# Signal_Conditioning.net
KiCad netlist of a schematic drawn in Altium Designer
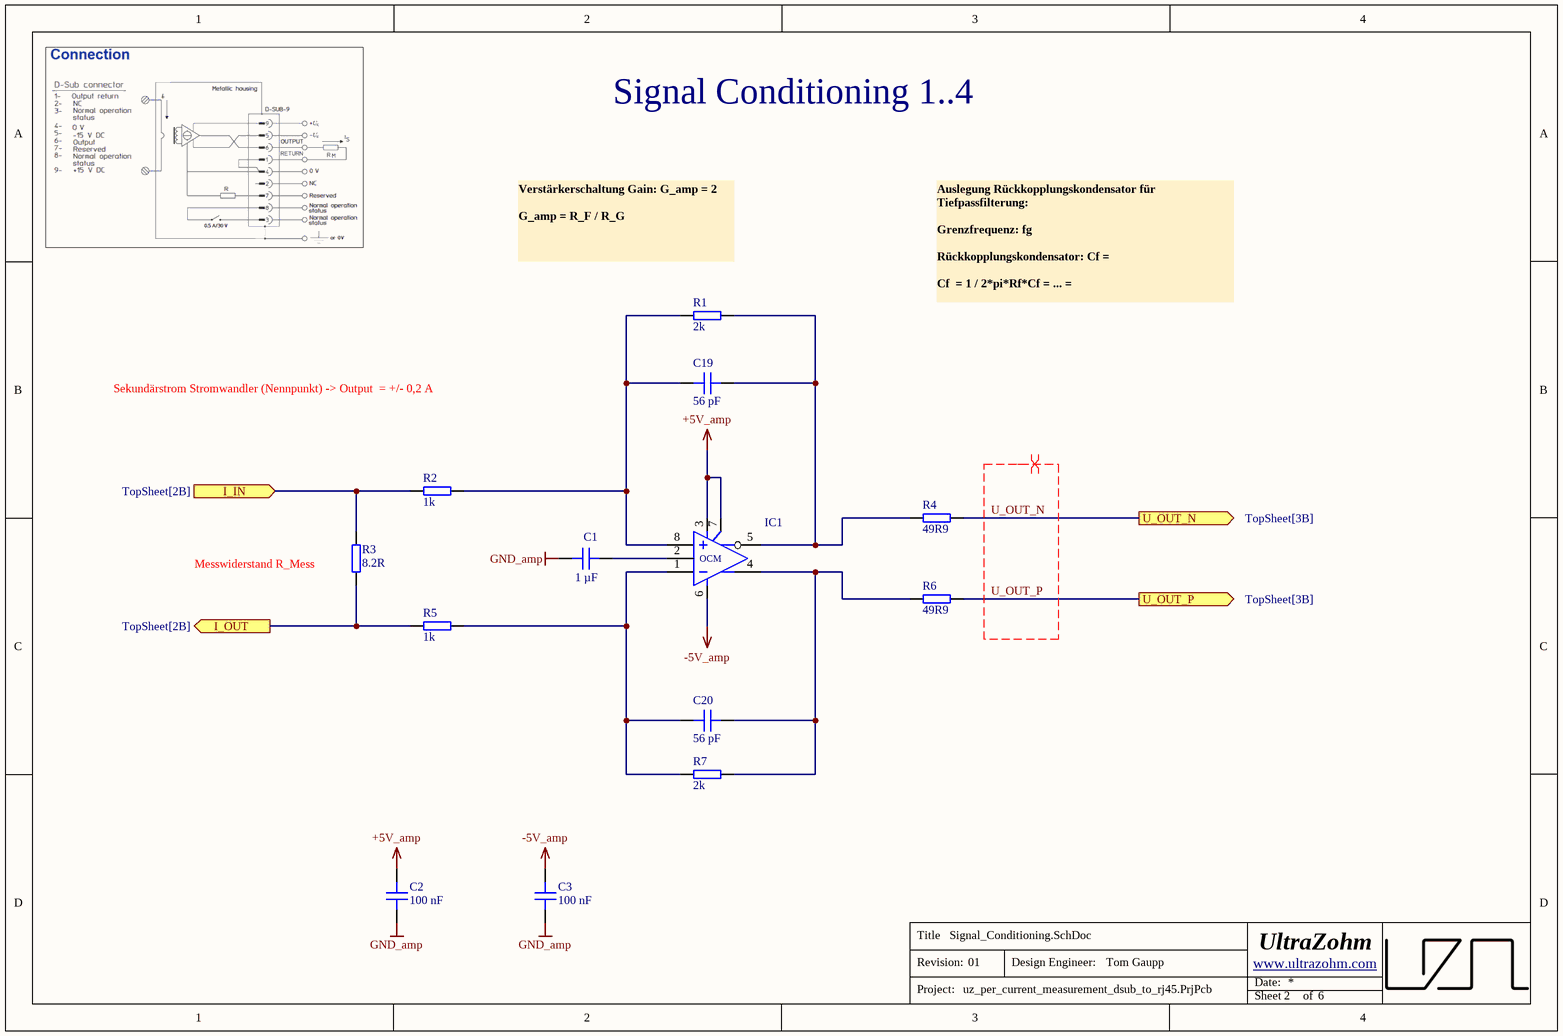
[diagram p0: Signal_Conditioning.SchDoc]

(export (version "E")
  (design (tool "Eeschema 10.0.6"))
  (components
    (comp (ref "C1")
      (value "1 µF")
      (footprint "C_0603")
      (description "50V 1uF X5R ±10% 0603  Multilayer Ceramic Capacitors MLCC - SMD/SMT ROHS")
      (fields
        (field (name "MANUFACTURER") "Samsung Electro-Mechanics")
        (field (name "MANUFACTURER PART NUMBER") "CL10A105KB8NNNC")
        (field (name "CREATED FROM") "MGremer")
      )
      (libsource (lib "user") (part "Capacitor"))
    )
    (comp (ref "C2")
      (value "100 nF")
      (footprint "C_0603")
      (description "Capacitor 0603, 50 VDC, 100nF, X7R")
      (fields
        (field (name "MANUFACTURER PART NUMBER") "C0603C104K5RAC3121")
        (field (name "MANUFACTURER") "KEMET")
        (field (name "CREATED FROM") "DHufnagel")
      )
      (libsource (lib "user") (part "Capacitor"))
    )
    (comp (ref "C3")
      (value "100 nF")
      (footprint "C_0603")
      (description "Capacitor 0603, 50 VDC, 100nF, X7R")
      (fields
        (field (name "MANUFACTURER PART NUMBER") "C0603C104K5RAC3121")
        (field (name "MANUFACTURER") "KEMET")
        (field (name "CREATED FROM") "DHufnagel")
      )
      (libsource (lib "user") (part "Capacitor"))
    )
    (comp (ref "C19")
      (value "56 pF")
      (footprint "C_0603")
      (description "Capacitor 0603, 50 VDC, 56 pF, C0G")
      (fields
        (field (name "MANUFACTURER PART NUMBER") "CL10C560JB8NNNC")
        (field (name "MANUFACTURER") "Samsung Electro-Mechanics")
        (field (name "CREATED FROM") "DHufnagel")
      )
      (libsource (lib "user") (part "Capacitor"))
    )
    (comp (ref "C20")
      (value "56 pF")
      (footprint "C_0603")
      (description "Capacitor 0603, 50 VDC, 56 pF, C0G")
      (fields
        (field (name "MANUFACTURER PART NUMBER") "CL10C560JB8NNNC")
        (field (name "MANUFACTURER") "Samsung Electro-Mechanics")
        (field (name "CREATED FROM") "DHufnagel")
      )
      (libsource (lib "user") (part "Capacitor"))
    )
    (comp (ref "IC1")
      (value "ADA4940-1ARZ-R7")
      (footprint "SOIC-8-N")
      (description "Differential ADC Driver")
      (fields
        (field (name "MANUFACTURER") "Analog Devices")
        (field (name "LCSC PART NUMBER") "C730049")
        (field (name "CREATED FROM") "MGremer")
      )
      (libsource (lib "user") (part "ADA4940-1ARZ"))
    )
    (comp (ref "R1")
      (value "2k")
      (footprint "RES 1206_3216")
      (description "2kΩ ±0.1% 250mW 1206")
      (fields
        (field (name "MANUFACTURER PART NUMBER") "ERA-8AEB202V")
        (field (name "MANUFACTURER") "Panasonic")
        (field (name "CREATED FROM") "TGaupp")
      )
      (libsource (lib "user") (part "Resistor"))
    )
    (comp (ref "R2")
      (value "1k")
      (footprint "RES 1206_3216")
      (description "SMD resistor 1/4W 1.0Kohm 0.1% 25ppm")
      (fields
        (field (name "MANUFACTURER PART NUMBER") "ERA-8AEB102V")
        (field (name "MANUFACTURER") "Panasonic")
        (field (name "CREATED FROM") "TGaupp")
      )
      (libsource (lib "user") (part "Resistor"))
    )
    (comp (ref "R3")
      (value "8.2R")
      (footprint "RES 2010_5025")
      (description "-55℃~+155℃ 200V 750mW 8.2Ω Thick Film Resistor ±1% ±200ppm/℃ 2010 Chip Resistor")
      (fields
        (field (name "MANUFACTURER PART NUMBER") "RC2010FK-078R2L")
        (field (name "MANUFACTURER") "YAEGO")
        (field (name "CREATED FROM") "TGaupp")
      )
      (libsource (lib "user") (part "Resistor"))
    )
    (comp (ref "R4")
      (value "49R9")
      (footprint "RES 0603_1608")
      (description "100mW Thick Film Resistors ±100ppm/℃ ±1% 49.9Ω 0603 Chip Resistor - Surface Mount ROHS")
      (fields
        (field (name "MANUFACTURER PART NUMBER") "RC0603FR-0749R9L")
        (field (name "MANUFACTURER") "YAGEO")
        (field (name "CREATED FROM") "AGeiger")
      )
      (libsource (lib "user") (part "Resistor"))
    )
    (comp (ref "R5")
      (value "1k")
      (footprint "RES 1206_3216")
      (description "SMD resistor 1/4W 1.0Kohm 0.1% 25ppm")
      (fields
        (field (name "MANUFACTURER PART NUMBER") "ERA-8AEB102V")
        (field (name "MANUFACTURER") "Panasonic")
        (field (name "CREATED FROM") "TGaupp")
      )
      (libsource (lib "user") (part "Resistor"))
    )
    (comp (ref "R6")
      (value "49R9")
      (footprint "RES 0603_1608")
      (description "100mW Thick Film Resistors ±100ppm/℃ ±1% 49.9Ω 0603 Chip Resistor - Surface Mount ROHS")
      (fields
        (field (name "MANUFACTURER PART NUMBER") "RC0603FR-0749R9L")
        (field (name "MANUFACTURER") "YAGEO")
        (field (name "CREATED FROM") "AGeiger")
      )
      (libsource (lib "user") (part "Resistor"))
    )
    (comp (ref "R7")
      (value "2k")
      (footprint "RES 1206_3216")
      (description "2kΩ ±0.1% 250mW 1206")
      (fields
        (field (name "MANUFACTURER PART NUMBER") "ERA-8AEB202V")
        (field (name "MANUFACTURER") "Panasonic")
        (field (name "CREATED FROM") "TGaupp")
      )
      (libsource (lib "user") (part "Resistor"))
    )
  )
  (nets
    (net (code "1") (name "+5V_amp") (class "Default")
      (node (ref "C2") (pin "2") (pinfunction "2_2") (pintype "passive"))
      (node (ref "IC1") (pin "3") (pinfunction "V+_3") (pintype "passive"))
      (node (ref "IC1") (pin "7") (pinfunction "EN_7") (pintype "passive"))
    )
    (net (code "2") (name "-5V_amp") (class "Default")
      (node (ref "C3") (pin "2") (pinfunction "2_2") (pintype "passive"))
      (node (ref "IC1") (pin "6") (pinfunction "V-_6") (pintype "passive"))
    )
    (net (code "3") (name "/I_IN") (class "Default")
      (node (ref "R2") (pin "1") (pinfunction "1_1") (pintype "passive"))
      (node (ref "R3") (pin "2") (pinfunction "2_2") (pintype "passive"))
    )
    (net (code "4") (name "/I_OUT") (class "Default")
      (node (ref "R3") (pin "1") (pinfunction "1_1") (pintype "passive"))
      (node (ref "R5") (pin "1") (pinfunction "1_1") (pintype "passive"))
    )
    (net (code "5") (name "/U_OUT_N") (class "Default")
      (node (ref "R4") (pin "2") (pinfunction "2_2") (pintype "passive"))
    )
    (net (code "6") (name "/U_OUT_P") (class "Default")
      (node (ref "R6") (pin "2") (pinfunction "2_2") (pintype "passive"))
    )
    (net (code "7") (name "GND_amp") (class "Default")
      (node (ref "C1") (pin "1") (pinfunction "1_1") (pintype "passive"))
      (node (ref "C2") (pin "1") (pinfunction "1_1") (pintype "passive"))
      (node (ref "C3") (pin "1") (pinfunction "1_1") (pintype "passive"))
    )
    (net (code "8") (name "Net-(C19-Pad2)") (class "Default")
      (node (ref "C19") (pin "2") (pinfunction "2_2") (pintype "passive"))
      (node (ref "IC1") (pin "5") (pinfunction "Out_5") (pintype "passive"))
      (node (ref "R1") (pin "2") (pinfunction "2_2") (pintype "passive"))
      (node (ref "R4") (pin "1") (pinfunction "1_1") (pintype "passive"))
    )
    (net (code "9") (name "Net-(C20-Pad2)") (class "Default")
      (node (ref "C20") (pin "2") (pinfunction "2_2") (pintype "passive"))
      (node (ref "IC1") (pin "4") (pinfunction "Out_4") (pintype "passive"))
      (node (ref "R6") (pin "1") (pinfunction "1_1") (pintype "passive"))
      (node (ref "R7") (pin "2") (pinfunction "2_2") (pintype "passive"))
    )
    (net (code "10") (name "Net-(IC1-+)") (class "Default")
      (node (ref "C19") (pin "1") (pinfunction "1_1") (pintype "passive"))
      (node (ref "IC1") (pin "8") (pinfunction "+_8") (pintype "passive"))
      (node (ref "R1") (pin "1") (pinfunction "1_1") (pintype "passive"))
      (node (ref "R2") (pin "2") (pinfunction "2_2") (pintype "passive"))
    )
    (net (code "11") (name "Net-(IC1--)") (class "Default")
      (node (ref "C20") (pin "1") (pinfunction "1_1") (pintype "passive"))
      (node (ref "IC1") (pin "1") (pinfunction "-_1") (pintype "passive"))
      (node (ref "R5") (pin "2") (pinfunction "2_2") (pintype "passive"))
      (node (ref "R7") (pin "1") (pinfunction "1_1") (pintype "passive"))
    )
    (net (code "12") (name "Net-(IC1-OCM)") (class "Default")
      (node (ref "C1") (pin "2") (pinfunction "2_2") (pintype "passive"))
      (node (ref "IC1") (pin "2") (pinfunction "OCM_2") (pintype "passive"))
    )
  )
)
